# payloads.net
KiCad netlist of a schematic drawn in EAGLE
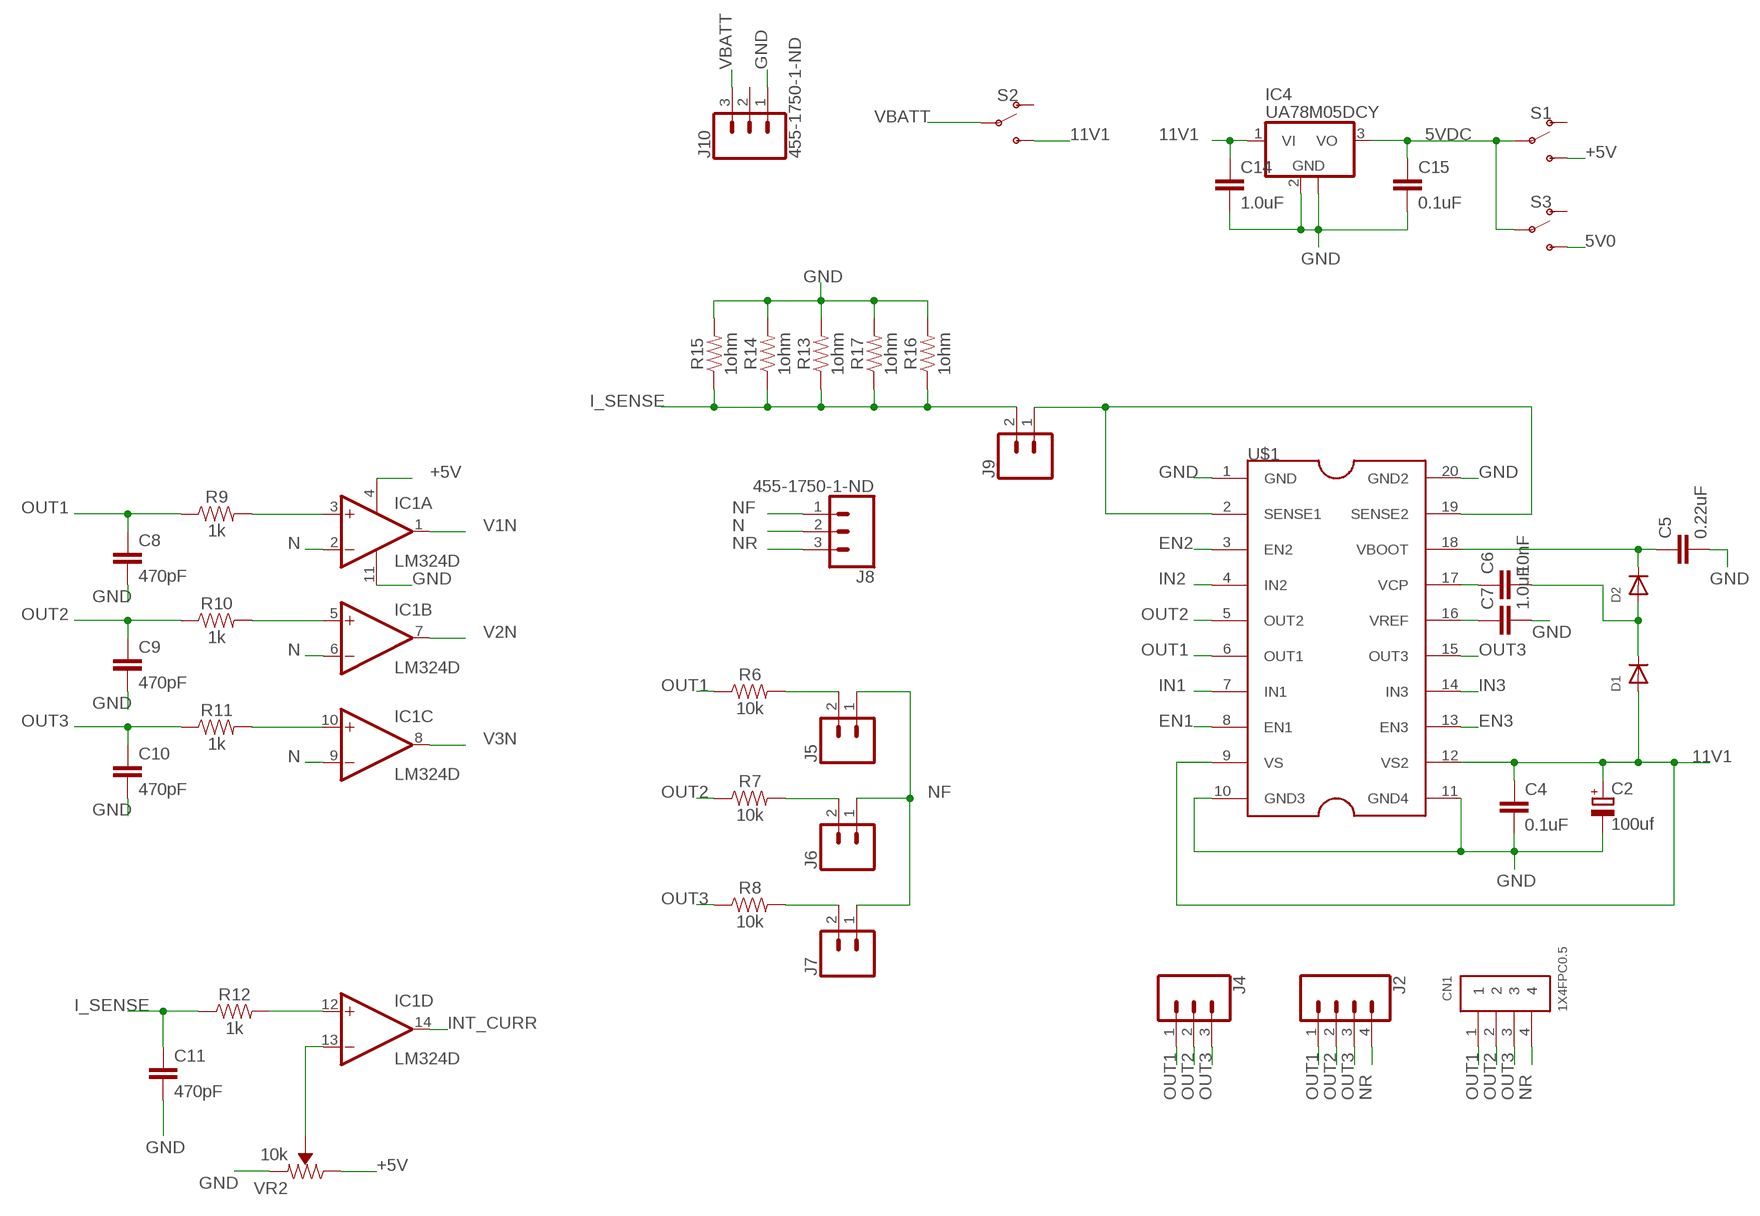
[diagram p0: schematic, sheet 1, part 1 of 2]
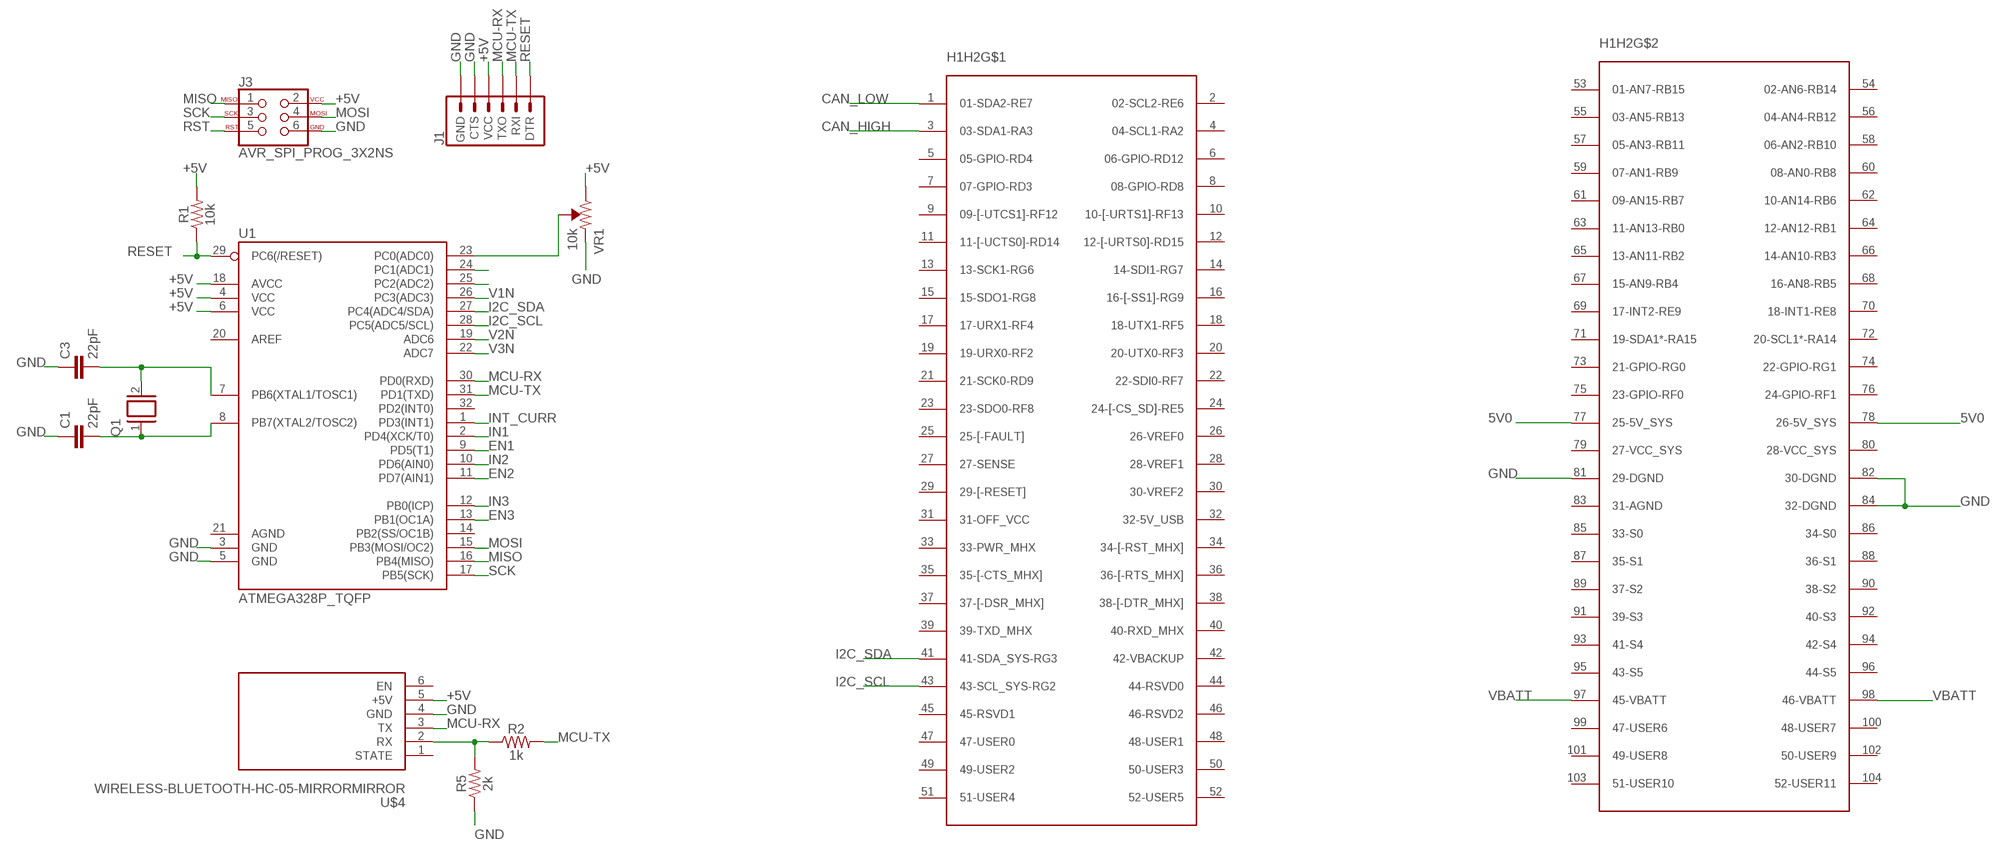
[diagram p1: schematic, sheet 1, part 2 of 2]

(export (version "E")
  (design (tool "Eeschema 10.0.6"))
  (components
    (comp (ref "C1")
      (value "22pF")
      (footprint "eagle-import:1206")
      (libsource (lib "eagle-import") (part "2.2UF-1206-50V-10%"))
    )
    (comp (ref "C2")
      (value "100uf")
      (footprint "eagle-import:C_6032-28R")
      (libsource (lib "eagle-import") (part "CPOL-EUC/6032-28R"))
    )
    (comp (ref "C3")
      (value "22pF")
      (footprint "eagle-import:1206")
      (libsource (lib "eagle-import") (part "2.2UF-1206-50V-10%"))
    )
    (comp (ref "C4")
      (value "0.1uF")
      (footprint "eagle-import:0603")
      (libsource (lib "eagle-import") (part "0.1UF-0603-100V-10%"))
    )
    (comp (ref "C5")
      (value "0.22uF")
      (footprint "eagle-import:0603")
      (libsource (lib "eagle-import") (part "0.22UF-0603-25V-10%"))
    )
    (comp (ref "C6")
      (value "10nF")
      (footprint "eagle-import:0603")
      (libsource (lib "eagle-import") (part "10NF-0603-50V-10%"))
    )
    (comp (ref "C7")
      (value "1.0uF")
      (footprint "eagle-import:0603")
      (libsource (lib "eagle-import") (part "1.0UF-0603-16V-10%"))
    )
    (comp (ref "C8")
      (value "470pF")
      (footprint "eagle-import:0603")
      (libsource (lib "eagle-import") (part "470PF-0603-50V-5%"))
    )
    (comp (ref "C9")
      (value "470pF")
      (footprint "eagle-import:0603")
      (libsource (lib "eagle-import") (part "470PF-0603-50V-5%"))
    )
    (comp (ref "C10")
      (value "470pF")
      (footprint "eagle-import:0603")
      (libsource (lib "eagle-import") (part "470PF-0603-50V-5%"))
    )
    (comp (ref "C11")
      (value "470pF")
      (footprint "eagle-import:0603")
      (libsource (lib "eagle-import") (part "470PF-0603-50V-5%"))
    )
    (comp (ref "C14")
      (value "1.0uF")
      (footprint "eagle-import:1206")
      (libsource (lib "eagle-import") (part "1.0UF-1206-50V-10%"))
    )
    (comp (ref "C15")
      (value "0.1uF")
      (footprint "eagle-import:1206")
      (libsource (lib "eagle-import") (part "1.0UF-1206-50V-10%"))
    )
    (comp (ref "CN1")
      (value "1X4FPC0.5")
      (footprint "eagle-import:FPC_0.5MM-4")
      (libsource (lib "eagle-import") (part "1X4FPC0.5"))
    )
    (comp (ref "D1")
      (value "DIODESOD-123")
      (footprint "eagle-import:SOD-123")
      (libsource (lib "eagle-import") (part "DIODESOD-123"))
    )
    (comp (ref "D2")
      (value "DIODESOD-123")
      (footprint "eagle-import:SOD-123")
      (libsource (lib "eagle-import") (part "DIODESOD-123"))
    )
    (comp (ref "H1H2")
      (value "PC104_CONN")
      (footprint "eagle-import:PC_104")
      (libsource (lib "eagle-import") (part "PC104_CONN"))
    )
    (comp (ref "IC1")
      (value "LM324D")
      (footprint "eagle-import:SO14")
      (libsource (lib "eagle-import") (part "LM324D"))
    )
    (comp (ref "IC4")
      (value "UA78M05DCY")
      (footprint "eagle-import:SOT223")
      (libsource (lib "eagle-import") (part "UA78MDCY05"))
    )
    (comp (ref "J1")
      (value "6_PIN_SERIAL_TARGET")
      (footprint "eagle-import:1X06")
      (libsource (lib "eagle-import") (part "6_PIN_SERIAL_TARGET"))
    )
    (comp (ref "J2")
      (value "CONN_04")
      (footprint "eagle-import:1X04")
      (libsource (lib "eagle-import") (part "CONN_04"))
    )
    (comp (ref "J3")
      (value "AVR_SPI_PROG_3X2NS")
      (footprint "eagle-import:2X3-NS")
      (libsource (lib "eagle-import") (part "AVR_SPI_PROG_3X2NS"))
    )
    (comp (ref "J4")
      (value "CONN_03-SCREW-5MM")
      (footprint "eagle-import:SCREWTERMINAL-5MM-3")
      (libsource (lib "eagle-import") (part "CONN_03-SCREW-5MM"))
    )
    (comp (ref "J5")
      (value "CONN_02")
      (footprint "eagle-import:1X02")
      (libsource (lib "eagle-import") (part "CONN_02"))
    )
    (comp (ref "J6")
      (value "CONN_02")
      (footprint "eagle-import:1X02")
      (libsource (lib "eagle-import") (part "CONN_02"))
    )
    (comp (ref "J7")
      (value "CONN_02")
      (footprint "eagle-import:1X02")
      (libsource (lib "eagle-import") (part "CONN_02"))
    )
    (comp (ref "J8")
      (value "455-1750-1-ND")
      (footprint "eagle-import:1X03")
      (libsource (lib "eagle-import") (part "CONN_03"))
    )
    (comp (ref "J9")
      (value "CONN_02")
      (footprint "eagle-import:1X02")
      (libsource (lib "eagle-import") (part "CONN_02"))
    )
    (comp (ref "J10")
      (value "455-1750-1-ND")
      (footprint "eagle-import:1X03")
      (libsource (lib "eagle-import") (part "CONN_03"))
    )
    (comp (ref "Q1")
      (value "XTAL/S")
      (footprint "eagle-import:QS")
      (libsource (lib "eagle-import") (part "XTAL/S"))
    )
    (comp (ref "R1")
      (value "10k")
      (footprint "eagle-import:1206")
      (libsource (lib "eagle-import") (part "RESISTOR1206"))
    )
    (comp (ref "R2")
      (value "1k")
      (footprint "eagle-import:AXIAL-0.3")
      (libsource (lib "eagle-import") (part "resistors-longpads_1KOHM-HORIZ-1/4W-5%"))
    )
    (comp (ref "R5")
      (value "2k")
      (footprint "eagle-import:AXIAL-0.3")
      (libsource (lib "eagle-import") (part "resistors-longpads_RESISTORAXIAL-0.3"))
    )
    (comp (ref "R6")
      (value "10k")
      (footprint "eagle-import:AXIAL-0.3")
      (libsource (lib "eagle-import") (part "10KOHM-HORIZ-1/4W-1%"))
    )
    (comp (ref "R7")
      (value "10k")
      (footprint "eagle-import:AXIAL-0.3")
      (libsource (lib "eagle-import") (part "10KOHM-HORIZ-1/4W-1%"))
    )
    (comp (ref "R8")
      (value "10k")
      (footprint "eagle-import:AXIAL-0.3")
      (libsource (lib "eagle-import") (part "10KOHM-HORIZ-1/4W-1%"))
    )
    (comp (ref "R9")
      (value "1k")
      (footprint "eagle-import:0603")
      (libsource (lib "eagle-import") (part "1KOHM-0603-1/10W-1%"))
    )
    (comp (ref "R10")
      (value "1k")
      (footprint "eagle-import:0603")
      (libsource (lib "eagle-import") (part "1KOHM-0603-1/10W-1%"))
    )
    (comp (ref "R11")
      (value "1k")
      (footprint "eagle-import:0603")
      (libsource (lib "eagle-import") (part "1KOHM-0603-1/10W-1%"))
    )
    (comp (ref "R12")
      (value "1k")
      (footprint "eagle-import:0603")
      (libsource (lib "eagle-import") (part "1KOHM-0603-1/10W-1%"))
    )
    (comp (ref "R13")
      (value "1ohm")
      (footprint "eagle-import:AXIAL-0.3")
      (libsource (lib "eagle-import") (part "1KOHM-HORIZ-1/4W-1%"))
    )
    (comp (ref "R14")
      (value "1ohm")
      (footprint "eagle-import:AXIAL-0.3")
      (libsource (lib "eagle-import") (part "1KOHM-HORIZ-1/4W-1%"))
    )
    (comp (ref "R15")
      (value "1ohm")
      (footprint "eagle-import:AXIAL-0.3")
      (libsource (lib "eagle-import") (part "1KOHM-HORIZ-1/4W-1%"))
    )
    (comp (ref "R16")
      (value "1ohm")
      (footprint "eagle-import:AXIAL-0.3")
      (libsource (lib "eagle-import") (part "1KOHM-HORIZ-1/4W-1%"))
    )
    (comp (ref "R17")
      (value "1ohm")
      (footprint "eagle-import:AXIAL-0.3")
      (libsource (lib "eagle-import") (part "1KOHM-HORIZ-1/4W-1%"))
    )
    (comp (ref "S1")
      (value "SWITCH-SPDT-PTH-11.6X4.0MM")
      (footprint "eagle-import:SWITCH_SPDT_PTH_11.6X4.0MM")
      (libsource (lib "eagle-import") (part "SWITCH-SPDT-PTH-11.6X4.0MM"))
    )
    (comp (ref "S2")
      (value "SWITCH-SPDT-PTH-11.6X4.0MM")
      (footprint "eagle-import:SWITCH_SPDT_PTH_11.6X4.0MM")
      (libsource (lib "eagle-import") (part "SWITCH-SPDT-PTH-11.6X4.0MM"))
    )
    (comp (ref "S3")
      (value "SWITCH-SPDT-PTH-11.6X4.0MM")
      (footprint "eagle-import:SWITCH_SPDT_PTH_11.6X4.0MM")
      (libsource (lib "eagle-import") (part "SWITCH-SPDT-PTH-11.6X4.0MM"))
    )
    (comp (ref "U$1")
      (value "L6234PD")
      (footprint "eagle-import:SO20")
      (libsource (lib "eagle-import") (part "L6234PD"))
    )
    (comp (ref "U$4")
      (value "WIRELESS-BLUETOOTH-HC-05-MIRRORMIRROR")
      (footprint "eagle-import:WIRELESS-BLUETOOTH-HC-05-MIRROR")
      (libsource (lib "eagle-import") (part "WIRELESS-BLUETOOTH-HC-05-MIRRORMIRROR"))
    )
    (comp (ref "U1")
      (value "ATMEGA328P_TQFP")
      (footprint "eagle-import:TQFP32-08")
      (libsource (lib "eagle-import") (part "ATMEGA328P_TQFP"))
    )
    (comp (ref "VR1")
      (value "10k")
      (footprint "eagle-import:TRIMPOT-PTH-3386U")
      (libsource (lib "eagle-import") (part "TRIMPOT-PTH-10MM-KNOB-1/2W-10%"))
    )
    (comp (ref "VR2")
      (value "10k")
      (footprint "eagle-import:TRIMPOT-PTH-3386U")
      (libsource (lib "eagle-import") (part "TRIMPOT-PTH-10MM-KNOB-1/2W-10%"))
    )
  )
  (nets
    (net (code "1") (name "/+5V") (class "Default")
      (node (ref "IC1") (pin "4") (pinfunction "V+_4") (pintype "power_in"))
      (node (ref "J1") (pin "4") (pinfunction "VCC_4") (pintype "passive"))
      (node (ref "J3") (pin "2") (pinfunction "2_2") (pintype "passive"))
      (node (ref "R1") (pin "2") (pinfunction "2_2") (pintype "passive"))
      (node (ref "S1") (pin "3") (pinfunction "S_3") (pintype "passive"))
      (node (ref "U$4") (pin "5") (pinfunction "+5V_5") (pintype "power_in"))
      (node (ref "U1") (pin "18") (pinfunction "AVCC_18") (pintype "bidirectional"))
      (node (ref "U1") (pin "4") (pinfunction "VCC_4") (pintype "bidirectional"))
      (node (ref "U1") (pin "6") (pinfunction "VCC_6") (pintype "bidirectional"))
      (node (ref "VR1") (pin "3") (pinfunction "CW_3") (pintype "passive"))
      (node (ref "VR2") (pin "3") (pinfunction "CW_3") (pintype "passive"))
    )
    (net (code "2") (name "/5V0") (class "Default")
      (node (ref "H1H2") (pin "77") (pinfunction "25-5V_SYS_77") (pintype "bidirectional"))
      (node (ref "H1H2") (pin "78") (pinfunction "26-5V_SYS_78") (pintype "bidirectional"))
      (node (ref "S3") (pin "3") (pinfunction "S_3") (pintype "passive"))
    )
    (net (code "3") (name "/5VDC") (class "Default")
      (node (ref "C15") (pin "1") (pinfunction "1_1") (pintype "passive"))
      (node (ref "IC4") (pin "3") (pinfunction "VO_3") (pintype "passive"))
      (node (ref "S1") (pin "2") (pinfunction "P_2") (pintype "passive"))
      (node (ref "S3") (pin "2") (pinfunction "P_2") (pintype "passive"))
    )
    (net (code "4") (name "/11V1") (class "Default")
      (node (ref "C14") (pin "1") (pinfunction "1_1") (pintype "passive"))
      (node (ref "C2") (pin "+") (pinfunction "+_+") (pintype "passive"))
      (node (ref "C4") (pin "1") (pinfunction "1_1") (pintype "passive"))
      (node (ref "D1") (pin "A") (pinfunction "A_A") (pintype "passive"))
      (node (ref "IC4") (pin "1") (pinfunction "VI_1") (pintype "input"))
      (node (ref "S2") (pin "3") (pinfunction "S_3") (pintype "passive"))
      (node (ref "U$1") (pin "12") (pinfunction "VS2_12") (pintype "power_in"))
      (node (ref "U$1") (pin "9") (pinfunction "VS_9") (pintype "power_in"))
    )
    (net (code "5") (name "/CAN_HIGH") (class "Default")
      (node (ref "H1H2") (pin "3") (pinfunction "03-SDA1-RA3_3") (pintype "bidirectional"))
    )
    (net (code "6") (name "/CAN_LOW") (class "Default")
      (node (ref "H1H2") (pin "1") (pinfunction "01-SDA2-RE7_1") (pintype "bidirectional"))
    )
    (net (code "7") (name "/EN1") (class "Default")
      (node (ref "U$1") (pin "8") (pinfunction "EN1_8") (pintype "bidirectional"))
      (node (ref "U1") (pin "9") (pinfunction "PD5(T1)_9") (pintype "bidirectional"))
    )
    (net (code "8") (name "/EN2") (class "Default")
      (node (ref "U$1") (pin "3") (pinfunction "EN2_3") (pintype "bidirectional"))
      (node (ref "U1") (pin "11") (pinfunction "PD7(AIN1)_11") (pintype "bidirectional"))
    )
    (net (code "9") (name "/EN3") (class "Default")
      (node (ref "U$1") (pin "13") (pinfunction "EN3_13") (pintype "bidirectional"))
      (node (ref "U1") (pin "13") (pinfunction "PB1(OC1A)_13") (pintype "bidirectional"))
    )
    (net (code "10") (name "/GND") (class "Default")
      (node (ref "C1") (pin "1") (pinfunction "1_1") (pintype "passive"))
      (node (ref "C10") (pin "2") (pinfunction "2_2") (pintype "passive"))
      (node (ref "C11") (pin "2") (pinfunction "2_2") (pintype "passive"))
      (node (ref "C14") (pin "2") (pinfunction "2_2") (pintype "passive"))
      (node (ref "C15") (pin "2") (pinfunction "2_2") (pintype "passive"))
      (node (ref "C2") (pin "-") (pinfunction "-_-") (pintype "passive"))
      (node (ref "C3") (pin "1") (pinfunction "1_1") (pintype "passive"))
      (node (ref "C4") (pin "2") (pinfunction "2_2") (pintype "passive"))
      (node (ref "C5") (pin "2") (pinfunction "2_2") (pintype "passive"))
      (node (ref "C7") (pin "2") (pinfunction "2_2") (pintype "passive"))
      (node (ref "C8") (pin "2") (pinfunction "2_2") (pintype "passive"))
      (node (ref "C9") (pin "2") (pinfunction "2_2") (pintype "passive"))
      (node (ref "H1H2") (pin "81") (pinfunction "29-DGND_81") (pintype "bidirectional"))
      (node (ref "H1H2") (pin "82") (pinfunction "30-DGND_82") (pintype "bidirectional"))
      (node (ref "H1H2") (pin "84") (pinfunction "32-DGND_84") (pintype "bidirectional"))
      (node (ref "IC1") (pin "11") (pinfunction "V-_11") (pintype "power_in"))
      (node (ref "IC4") (pin "2") (pinfunction "GND_2") (pintype "passive"))
      (node (ref "IC4") (pin "4") (pinfunction "GND_4") (pintype "passive"))
      (node (ref "J1") (pin "5") (pinfunction "CTS_5") (pintype "passive"))
      (node (ref "J1") (pin "6") (pinfunction "GND_6") (pintype "passive"))
      (node (ref "J10") (pin "1") (pinfunction "1_1") (pintype "passive"))
      (node (ref "J3") (pin "6") (pinfunction "6_6") (pintype "passive"))
      (node (ref "R13") (pin "P$2") (pinfunction "2_P$2") (pintype "passive"))
      (node (ref "R14") (pin "P$2") (pinfunction "2_P$2") (pintype "passive"))
      (node (ref "R15") (pin "P$2") (pinfunction "2_P$2") (pintype "passive"))
      (node (ref "R16") (pin "P$2") (pinfunction "2_P$2") (pintype "passive"))
      (node (ref "R17") (pin "P$2") (pinfunction "2_P$2") (pintype "passive"))
      (node (ref "R5") (pin "P$1") (pinfunction "1_P$1") (pintype "passive"))
      (node (ref "U$1") (pin "1") (pinfunction "GND_1") (pintype "bidirectional"))
      (node (ref "U$1") (pin "10") (pinfunction "GND3_10") (pintype "bidirectional"))
      (node (ref "U$1") (pin "11") (pinfunction "GND4_11") (pintype "bidirectional"))
      (node (ref "U$1") (pin "20") (pinfunction "GND2_20") (pintype "bidirectional"))
      (node (ref "U$4") (pin "4") (pinfunction "GND_4") (pintype "power_in"))
      (node (ref "U1") (pin "3") (pinfunction "GND_3") (pintype "bidirectional"))
      (node (ref "U1") (pin "5") (pinfunction "GND_5") (pintype "bidirectional"))
      (node (ref "VR1") (pin "1") (pinfunction "CCW_1") (pintype "passive"))
      (node (ref "VR2") (pin "1") (pinfunction "CCW_1") (pintype "passive"))
    )
    (net (code "11") (name "/I2C_SCL") (class "Default")
      (node (ref "H1H2") (pin "43") (pinfunction "43-SCL_SYS-RG2_43") (pintype "bidirectional"))
      (node (ref "U1") (pin "28") (pinfunction "PC5(ADC5/SCL)_28") (pintype "bidirectional"))
    )
    (net (code "12") (name "/I2C_SDA") (class "Default")
      (node (ref "H1H2") (pin "41") (pinfunction "41-SDA_SYS-RG3_41") (pintype "bidirectional"))
      (node (ref "U1") (pin "27") (pinfunction "PC4(ADC4/SDA)_27") (pintype "bidirectional"))
    )
    (net (code "13") (name "/IN1") (class "Default")
      (node (ref "U$1") (pin "7") (pinfunction "IN1_7") (pintype "bidirectional"))
      (node (ref "U1") (pin "2") (pinfunction "PD4(XCK/T0)_2") (pintype "bidirectional"))
    )
    (net (code "14") (name "/IN2") (class "Default")
      (node (ref "U$1") (pin "4") (pinfunction "IN2_4") (pintype "bidirectional"))
      (node (ref "U1") (pin "10") (pinfunction "PD6(AIN0)_10") (pintype "bidirectional"))
    )
    (net (code "15") (name "/IN3") (class "Default")
      (node (ref "U$1") (pin "14") (pinfunction "IN3_14") (pintype "bidirectional"))
      (node (ref "U1") (pin "12") (pinfunction "PB0(ICP)_12") (pintype "bidirectional"))
    )
    (net (code "16") (name "/INT_CURR") (class "Default")
      (node (ref "IC1") (pin "14") (pinfunction "OUT_14") (pintype "output"))
      (node (ref "U1") (pin "1") (pinfunction "PD3(INT1)_1") (pintype "bidirectional"))
    )
    (net (code "17") (name "/I_SENSE") (class "Default")
      (node (ref "C11") (pin "1") (pinfunction "1_1") (pintype "passive"))
      (node (ref "J9") (pin "2") (pinfunction "2_2") (pintype "passive"))
      (node (ref "R12") (pin "1") (pinfunction "1_1") (pintype "passive"))
      (node (ref "R13") (pin "P$1") (pinfunction "1_P$1") (pintype "passive"))
      (node (ref "R14") (pin "P$1") (pinfunction "1_P$1") (pintype "passive"))
      (node (ref "R15") (pin "P$1") (pinfunction "1_P$1") (pintype "passive"))
      (node (ref "R16") (pin "P$1") (pinfunction "1_P$1") (pintype "passive"))
      (node (ref "R17") (pin "P$1") (pinfunction "1_P$1") (pintype "passive"))
    )
    (net (code "18") (name "/MCU-RX") (class "Default")
      (node (ref "J1") (pin "3") (pinfunction "TXO_3") (pintype "passive"))
      (node (ref "U$4") (pin "3") (pinfunction "TX_3") (pintype "bidirectional"))
      (node (ref "U1") (pin "30") (pinfunction "PD0(RXD)_30") (pintype "bidirectional"))
    )
    (net (code "19") (name "/MCU-TX") (class "Default")
      (node (ref "J1") (pin "2") (pinfunction "RXI_2") (pintype "passive"))
      (node (ref "R2") (pin "P$2") (pinfunction "2_P$2") (pintype "passive"))
      (node (ref "U1") (pin "31") (pinfunction "PD1(TXD)_31") (pintype "bidirectional"))
    )
    (net (code "20") (name "/MISO") (class "Default")
      (node (ref "J3") (pin "1") (pinfunction "1_1") (pintype "passive"))
      (node (ref "U1") (pin "16") (pinfunction "PB4(MISO)_16") (pintype "bidirectional"))
    )
    (net (code "21") (name "/MOSI") (class "Default")
      (node (ref "J3") (pin "4") (pinfunction "4_4") (pintype "passive"))
      (node (ref "U1") (pin "15") (pinfunction "PB3(MOSI/OC2)_15") (pintype "bidirectional"))
    )
    (net (code "22") (name "/N") (class "Default")
      (node (ref "IC1") (pin "2") (pinfunction "-IN_2") (pintype "input"))
      (node (ref "IC1") (pin "6") (pinfunction "-IN_6") (pintype "input"))
      (node (ref "IC1") (pin "9") (pinfunction "-IN_9") (pintype "input"))
      (node (ref "J8") (pin "2") (pinfunction "2_2") (pintype "passive"))
    )
    (net (code "23") (name "/NF") (class "Default")
      (node (ref "J5") (pin "1") (pinfunction "1_1") (pintype "passive"))
      (node (ref "J6") (pin "1") (pinfunction "1_1") (pintype "passive"))
      (node (ref "J7") (pin "1") (pinfunction "1_1") (pintype "passive"))
      (node (ref "J8") (pin "1") (pinfunction "1_1") (pintype "passive"))
    )
    (net (code "24") (name "/NR") (class "Default")
      (node (ref "CN1") (pin "4") (pinfunction "4_4") (pintype "bidirectional"))
      (node (ref "J2") (pin "4") (pinfunction "4_4") (pintype "passive"))
      (node (ref "J8") (pin "3") (pinfunction "3_3") (pintype "passive"))
    )
    (net (code "25") (name "/OUT1") (class "Default")
      (node (ref "C8") (pin "1") (pinfunction "1_1") (pintype "passive"))
      (node (ref "CN1") (pin "1") (pinfunction "1_1") (pintype "bidirectional"))
      (node (ref "J2") (pin "1") (pinfunction "1_1") (pintype "passive"))
      (node (ref "J4") (pin "1") (pinfunction "1_1") (pintype "passive"))
      (node (ref "R6") (pin "P$1") (pinfunction "1_P$1") (pintype "passive"))
      (node (ref "R9") (pin "1") (pinfunction "1_1") (pintype "passive"))
      (node (ref "U$1") (pin "6") (pinfunction "OUT1_6") (pintype "bidirectional"))
    )
    (net (code "26") (name "/OUT2") (class "Default")
      (node (ref "C9") (pin "1") (pinfunction "1_1") (pintype "passive"))
      (node (ref "CN1") (pin "2") (pinfunction "2_2") (pintype "bidirectional"))
      (node (ref "J2") (pin "2") (pinfunction "2_2") (pintype "passive"))
      (node (ref "J4") (pin "2") (pinfunction "2_2") (pintype "passive"))
      (node (ref "R10") (pin "1") (pinfunction "1_1") (pintype "passive"))
      (node (ref "R7") (pin "P$1") (pinfunction "1_P$1") (pintype "passive"))
      (node (ref "U$1") (pin "5") (pinfunction "OUT2_5") (pintype "bidirectional"))
    )
    (net (code "27") (name "/OUT3") (class "Default")
      (node (ref "C10") (pin "1") (pinfunction "1_1") (pintype "passive"))
      (node (ref "CN1") (pin "3") (pinfunction "3_3") (pintype "bidirectional"))
      (node (ref "J2") (pin "3") (pinfunction "3_3") (pintype "passive"))
      (node (ref "J4") (pin "3") (pinfunction "3_3") (pintype "passive"))
      (node (ref "R11") (pin "1") (pinfunction "1_1") (pintype "passive"))
      (node (ref "R8") (pin "P$1") (pinfunction "1_P$1") (pintype "passive"))
      (node (ref "U$1") (pin "15") (pinfunction "OUT3_15") (pintype "bidirectional"))
    )
    (net (code "28") (name "/RESET") (class "Default")
      (node (ref "J1") (pin "1") (pinfunction "DTR_1") (pintype "passive"))
      (node (ref "R1") (pin "1") (pinfunction "1_1") (pintype "passive"))
      (node (ref "U1") (pin "29") (pinfunction "PC6(/RESET)_29") (pintype "bidirectional"))
    )
    (net (code "29") (name "/RST") (class "Default")
      (node (ref "J3") (pin "5") (pinfunction "5_5") (pintype "passive"))
    )
    (net (code "30") (name "/SCK") (class "Default")
      (node (ref "J3") (pin "3") (pinfunction "3_3") (pintype "passive"))
      (node (ref "U1") (pin "17") (pinfunction "PB5(SCK)_17") (pintype "bidirectional"))
    )
    (net (code "31") (name "/V1N") (class "Default")
      (node (ref "IC1") (pin "1") (pinfunction "OUT_1") (pintype "output"))
      (node (ref "U1") (pin "26") (pinfunction "PC3(ADC3)_26") (pintype "bidirectional"))
    )
    (net (code "32") (name "/V2N") (class "Default")
      (node (ref "IC1") (pin "7") (pinfunction "OUT_7") (pintype "output"))
      (node (ref "U1") (pin "19") (pinfunction "ADC6_19") (pintype "bidirectional"))
    )
    (net (code "33") (name "/V3N") (class "Default")
      (node (ref "IC1") (pin "8") (pinfunction "OUT_8") (pintype "output"))
      (node (ref "U1") (pin "22") (pinfunction "ADC7_22") (pintype "bidirectional"))
    )
    (net (code "34") (name "/VBATT") (class "Default")
      (node (ref "H1H2") (pin "97") (pinfunction "45-VBATT_97") (pintype "bidirectional"))
      (node (ref "H1H2") (pin "98") (pinfunction "46-VBATT_98") (pintype "bidirectional"))
      (node (ref "J10") (pin "3") (pinfunction "3_3") (pintype "passive"))
      (node (ref "S2") (pin "2") (pinfunction "P_2") (pintype "passive"))
    )
    (net (code "35") (name "Net-(C6-Pad2)") (class "Default")
      (node (ref "C6") (pin "2") (pinfunction "2_2") (pintype "passive"))
      (node (ref "D1") (pin "C") (pinfunction "C_C") (pintype "passive"))
      (node (ref "D2") (pin "A") (pinfunction "A_A") (pintype "passive"))
    )
    (net (code "36") (name "Net-(IC1A-+IN)") (class "Default")
      (node (ref "IC1") (pin "3") (pinfunction "+IN_3") (pintype "input"))
      (node (ref "R9") (pin "2") (pinfunction "2_2") (pintype "passive"))
    )
    (net (code "37") (name "Net-(IC1B-+IN)") (class "Default")
      (node (ref "IC1") (pin "5") (pinfunction "+IN_5") (pintype "input"))
      (node (ref "R10") (pin "2") (pinfunction "2_2") (pintype "passive"))
    )
    (net (code "38") (name "Net-(IC1C-+IN)") (class "Default")
      (node (ref "IC1") (pin "10") (pinfunction "+IN_10") (pintype "input"))
      (node (ref "R11") (pin "2") (pinfunction "2_2") (pintype "passive"))
    )
    (net (code "39") (name "Net-(IC1D-+IN)") (class "Default")
      (node (ref "IC1") (pin "12") (pinfunction "+IN_12") (pintype "input"))
      (node (ref "R12") (pin "2") (pinfunction "2_2") (pintype "passive"))
    )
    (net (code "40") (name "Net-(IC1D--IN)") (class "Default")
      (node (ref "IC1") (pin "13") (pinfunction "-IN_13") (pintype "input"))
      (node (ref "VR2") (pin "2") (pinfunction "WIPER_2") (pintype "passive"))
    )
    (net (code "41") (name "Net-(R2-1)") (class "Default")
      (node (ref "R2") (pin "P$1") (pinfunction "1_P$1") (pintype "passive"))
      (node (ref "R5") (pin "P$2") (pinfunction "2_P$2") (pintype "passive"))
      (node (ref "U$4") (pin "2") (pinfunction "RX_2") (pintype "bidirectional"))
    )
    (net (code "42") (name "Net-(R6-2)") (class "Default")
      (node (ref "J5") (pin "2") (pinfunction "2_2") (pintype "passive"))
      (node (ref "R6") (pin "P$2") (pinfunction "2_P$2") (pintype "passive"))
    )
    (net (code "43") (name "Net-(R7-2)") (class "Default")
      (node (ref "J6") (pin "2") (pinfunction "2_2") (pintype "passive"))
      (node (ref "R7") (pin "P$2") (pinfunction "2_P$2") (pintype "passive"))
    )
    (net (code "44") (name "Net-(R8-2)") (class "Default")
      (node (ref "J7") (pin "2") (pinfunction "2_2") (pintype "passive"))
      (node (ref "R8") (pin "P$2") (pinfunction "2_P$2") (pintype "passive"))
    )
    (net (code "45") (name "Net-(U$1-SENSE1)") (class "Default")
      (node (ref "J9") (pin "1") (pinfunction "1_1") (pintype "passive"))
      (node (ref "U$1") (pin "19") (pinfunction "SENSE2_19") (pintype "bidirectional"))
      (node (ref "U$1") (pin "2") (pinfunction "SENSE1_2") (pintype "bidirectional"))
    )
    (net (code "46") (name "Net-(U$1-VBOOT)") (class "Default")
      (node (ref "C5") (pin "1") (pinfunction "1_1") (pintype "passive"))
      (node (ref "D2") (pin "C") (pinfunction "C_C") (pintype "passive"))
      (node (ref "U$1") (pin "18") (pinfunction "VBOOT_18") (pintype "bidirectional"))
    )
    (net (code "47") (name "Net-(U$1-VCP)") (class "Default")
      (node (ref "C6") (pin "1") (pinfunction "1_1") (pintype "passive"))
      (node (ref "U$1") (pin "17") (pinfunction "VCP_17") (pintype "bidirectional"))
    )
    (net (code "48") (name "Net-(U$1-VREF)") (class "Default")
      (node (ref "C7") (pin "1") (pinfunction "1_1") (pintype "passive"))
      (node (ref "U$1") (pin "16") (pinfunction "VREF_16") (pintype "bidirectional"))
    )
    (net (code "49") (name "Net-(U1-PB6(XTAL1{slash}TOSC1))") (class "Default")
      (node (ref "C3") (pin "2") (pinfunction "2_2") (pintype "passive"))
      (node (ref "Q1") (pin "2") (pinfunction "2_2") (pintype "passive"))
      (node (ref "U1") (pin "7") (pinfunction "PB6(XTAL1/TOSC1)_7") (pintype "bidirectional"))
    )
    (net (code "50") (name "Net-(U1-PB7(XTAL2{slash}TOSC2))") (class "Default")
      (node (ref "C1") (pin "2") (pinfunction "2_2") (pintype "passive"))
      (node (ref "Q1") (pin "1") (pinfunction "1_1") (pintype "passive"))
      (node (ref "U1") (pin "8") (pinfunction "PB7(XTAL2/TOSC2)_8") (pintype "bidirectional"))
    )
    (net (code "51") (name "Net-(U1-PC0(ADC0))") (class "Default")
      (node (ref "U1") (pin "23") (pinfunction "PC0(ADC0)_23") (pintype "bidirectional"))
      (node (ref "VR1") (pin "2") (pinfunction "WIPER_2") (pintype "passive"))
    )
    (net (code "52") (name "unconnected-(H1H2A-02-SCL2-RE6-Pad2)") (class "Default")
      (node (ref "H1H2") (pin "2") (pinfunction "02-SCL2-RE6_2") (pintype "bidirectional"))
    )
    (net (code "53") (name "unconnected-(H1H2A-04-SCL1-RA2-Pad4)") (class "Default")
      (node (ref "H1H2") (pin "4") (pinfunction "04-SCL1-RA2_4") (pintype "bidirectional"))
    )
    (net (code "54") (name "unconnected-(H1H2A-05-GPIO-RD4-Pad5)") (class "Default")
      (node (ref "H1H2") (pin "5") (pinfunction "05-GPIO-RD4_5") (pintype "bidirectional"))
    )
    (net (code "55") (name "unconnected-(H1H2A-06-GPIO-RD12-Pad6)") (class "Default")
      (node (ref "H1H2") (pin "6") (pinfunction "06-GPIO-RD12_6") (pintype "bidirectional"))
    )
    (net (code "56") (name "unconnected-(H1H2A-07-GPIO-RD3-Pad7)") (class "Default")
      (node (ref "H1H2") (pin "7") (pinfunction "07-GPIO-RD3_7") (pintype "bidirectional"))
    )
    (net (code "57") (name "unconnected-(H1H2A-08-GPIO-RD8-Pad8)") (class "Default")
      (node (ref "H1H2") (pin "8") (pinfunction "08-GPIO-RD8_8") (pintype "bidirectional"))
    )
    (net (code "58") (name "unconnected-(H1H2A-09-[-UTCS1]-RF12-Pad9)") (class "Default")
      (node (ref "H1H2") (pin "9") (pinfunction "09-[-UTCS1]-RF12_9") (pintype "bidirectional"))
    )
    (net (code "59") (name "unconnected-(H1H2A-10-[-URTS1]-RF13-Pad10)") (class "Default")
      (node (ref "H1H2") (pin "10") (pinfunction "10-[-URTS1]-RF13_10") (pintype "bidirectional"))
    )
    (net (code "60") (name "unconnected-(H1H2A-11-[-UCTS0]-RD14-Pad11)") (class "Default")
      (node (ref "H1H2") (pin "11") (pinfunction "11-[-UCTS0]-RD14_11") (pintype "bidirectional"))
    )
    (net (code "61") (name "unconnected-(H1H2A-12-[-URTS0]-RD15-Pad12)") (class "Default")
      (node (ref "H1H2") (pin "12") (pinfunction "12-[-URTS0]-RD15_12") (pintype "bidirectional"))
    )
    (net (code "62") (name "unconnected-(H1H2A-13-SCK1-RG6-Pad13)") (class "Default")
      (node (ref "H1H2") (pin "13") (pinfunction "13-SCK1-RG6_13") (pintype "bidirectional"))
    )
    (net (code "63") (name "unconnected-(H1H2A-14-SDI1-RG7-Pad14)") (class "Default")
      (node (ref "H1H2") (pin "14") (pinfunction "14-SDI1-RG7_14") (pintype "bidirectional"))
    )
    (net (code "64") (name "unconnected-(H1H2A-15-SDO1-RG8-Pad15)") (class "Default")
      (node (ref "H1H2") (pin "15") (pinfunction "15-SDO1-RG8_15") (pintype "bidirectional"))
    )
    (net (code "65") (name "unconnected-(H1H2A-16-[-SS1]-RG9-Pad16)") (class "Default")
      (node (ref "H1H2") (pin "16") (pinfunction "16-[-SS1]-RG9_16") (pintype "bidirectional"))
    )
    (net (code "66") (name "unconnected-(H1H2A-17-URX1-RF4-Pad17)") (class "Default")
      (node (ref "H1H2") (pin "17") (pinfunction "17-URX1-RF4_17") (pintype "bidirectional"))
    )
    (net (code "67") (name "unconnected-(H1H2A-18-UTX1-RF5-Pad18)") (class "Default")
      (node (ref "H1H2") (pin "18") (pinfunction "18-UTX1-RF5_18") (pintype "bidirectional"))
    )
    (net (code "68") (name "unconnected-(H1H2A-19-URX0-RF2-Pad19)") (class "Default")
      (node (ref "H1H2") (pin "19") (pinfunction "19-URX0-RF2_19") (pintype "bidirectional"))
    )
    (net (code "69") (name "unconnected-(H1H2A-20-UTX0-RF3-Pad20)") (class "Default")
      (node (ref "H1H2") (pin "20") (pinfunction "20-UTX0-RF3_20") (pintype "bidirectional"))
    )
    (net (code "70") (name "unconnected-(H1H2A-21-SCK0-RD9-Pad21)") (class "Default")
      (node (ref "H1H2") (pin "21") (pinfunction "21-SCK0-RD9_21") (pintype "bidirectional"))
    )
    (net (code "71") (name "unconnected-(H1H2A-22-SDI0-RF7-Pad22)") (class "Default")
      (node (ref "H1H2") (pin "22") (pinfunction "22-SDI0-RF7_22") (pintype "bidirectional"))
    )
    (net (code "72") (name "unconnected-(H1H2A-23-SDO0-RF8-Pad23)") (class "Default")
      (node (ref "H1H2") (pin "23") (pinfunction "23-SDO0-RF8_23") (pintype "bidirectional"))
    )
    (net (code "73") (name "unconnected-(H1H2A-24-[-CS_SD]-RE5-Pad24)") (class "Default")
      (node (ref "H1H2") (pin "24") (pinfunction "24-[-CS_SD]-RE5_24") (pintype "bidirectional"))
    )
    (net (code "74") (name "unconnected-(H1H2A-25-[-FAULT]-Pad25)") (class "Default")
      (node (ref "H1H2") (pin "25") (pinfunction "25-[-FAULT]_25") (pintype "bidirectional"))
    )
    (net (code "75") (name "unconnected-(H1H2A-26-VREF0-Pad26)") (class "Default")
      (node (ref "H1H2") (pin "26") (pinfunction "26-VREF0_26") (pintype "bidirectional"))
    )
    (net (code "76") (name "unconnected-(H1H2A-27-SENSE-Pad27)") (class "Default")
      (node (ref "H1H2") (pin "27") (pinfunction "27-SENSE_27") (pintype "bidirectional"))
    )
    (net (code "77") (name "unconnected-(H1H2A-28-VREF1-Pad28)") (class "Default")
      (node (ref "H1H2") (pin "28") (pinfunction "28-VREF1_28") (pintype "bidirectional"))
    )
    (net (code "78") (name "unconnected-(H1H2A-29-[-RESET]-Pad29)") (class "Default")
      (node (ref "H1H2") (pin "29") (pinfunction "29-[-RESET]_29") (pintype "bidirectional"))
    )
    (net (code "79") (name "unconnected-(H1H2A-30-VREF2-Pad30)") (class "Default")
      (node (ref "H1H2") (pin "30") (pinfunction "30-VREF2_30") (pintype "bidirectional"))
    )
    (net (code "80") (name "unconnected-(H1H2A-31-OFF_VCC-Pad31)") (class "Default")
      (node (ref "H1H2") (pin "31") (pinfunction "31-OFF_VCC_31") (pintype "bidirectional"))
    )
    (net (code "81") (name "unconnected-(H1H2A-32-5V_USB-Pad32)") (class "Default")
      (node (ref "H1H2") (pin "32") (pinfunction "32-5V_USB_32") (pintype "bidirectional"))
    )
    (net (code "82") (name "unconnected-(H1H2A-33-PWR_MHX-Pad33)") (class "Default")
      (node (ref "H1H2") (pin "33") (pinfunction "33-PWR_MHX_33") (pintype "bidirectional"))
    )
    (net (code "83") (name "unconnected-(H1H2A-34-[-RST_MHX]-Pad34)") (class "Default")
      (node (ref "H1H2") (pin "34") (pinfunction "34-[-RST_MHX]_34") (pintype "bidirectional"))
    )
    (net (code "84") (name "unconnected-(H1H2A-35-[-CTS_MHX]-Pad35)") (class "Default")
      (node (ref "H1H2") (pin "35") (pinfunction "35-[-CTS_MHX]_35") (pintype "bidirectional"))
    )
    (net (code "85") (name "unconnected-(H1H2A-36-[-RTS_MHX]-Pad36)") (class "Default")
      (node (ref "H1H2") (pin "36") (pinfunction "36-[-RTS_MHX]_36") (pintype "bidirectional"))
    )
    (net (code "86") (name "unconnected-(H1H2A-37-[-DSR_MHX]-Pad37)") (class "Default")
      (node (ref "H1H2") (pin "37") (pinfunction "37-[-DSR_MHX]_37") (pintype "bidirectional"))
    )
    (net (code "87") (name "unconnected-(H1H2A-38-[-DTR_MHX]-Pad38)") (class "Default")
      (node (ref "H1H2") (pin "38") (pinfunction "38-[-DTR_MHX]_38") (pintype "bidirectional"))
    )
    (net (code "88") (name "unconnected-(H1H2A-39-TXD_MHX-Pad39)") (class "Default")
      (node (ref "H1H2") (pin "39") (pinfunction "39-TXD_MHX_39") (pintype "bidirectional"))
    )
    (net (code "89") (name "unconnected-(H1H2A-40-RXD_MHX-Pad40)") (class "Default")
      (node (ref "H1H2") (pin "40") (pinfunction "40-RXD_MHX_40") (pintype "bidirectional"))
    )
    (net (code "90") (name "unconnected-(H1H2A-42-VBACKUP-Pad42)") (class "Default")
      (node (ref "H1H2") (pin "42") (pinfunction "42-VBACKUP_42") (pintype "bidirectional"))
    )
    (net (code "91") (name "unconnected-(H1H2A-44-RSVD0-Pad44)") (class "Default")
      (node (ref "H1H2") (pin "44") (pinfunction "44-RSVD0_44") (pintype "bidirectional"))
    )
    (net (code "92") (name "unconnected-(H1H2A-45-RSVD1-Pad45)") (class "Default")
      (node (ref "H1H2") (pin "45") (pinfunction "45-RSVD1_45") (pintype "bidirectional"))
    )
    (net (code "93") (name "unconnected-(H1H2A-46-RSVD2-Pad46)") (class "Default")
      (node (ref "H1H2") (pin "46") (pinfunction "46-RSVD2_46") (pintype "bidirectional"))
    )
    (net (code "94") (name "unconnected-(H1H2A-47-USER0-Pad47)") (class "Default")
      (node (ref "H1H2") (pin "47") (pinfunction "47-USER0_47") (pintype "bidirectional"))
    )
    (net (code "95") (name "unconnected-(H1H2A-48-USER1-Pad48)") (class "Default")
      (node (ref "H1H2") (pin "48") (pinfunction "48-USER1_48") (pintype "bidirectional"))
    )
    (net (code "96") (name "unconnected-(H1H2A-49-USER2-Pad49)") (class "Default")
      (node (ref "H1H2") (pin "49") (pinfunction "49-USER2_49") (pintype "bidirectional"))
    )
    (net (code "97") (name "unconnected-(H1H2A-50-USER3-Pad50)") (class "Default")
      (node (ref "H1H2") (pin "50") (pinfunction "50-USER3_50") (pintype "bidirectional"))
    )
    (net (code "98") (name "unconnected-(H1H2A-51-USER4-Pad51)") (class "Default")
      (node (ref "H1H2") (pin "51") (pinfunction "51-USER4_51") (pintype "bidirectional"))
    )
    (net (code "99") (name "unconnected-(H1H2A-52-USER5-Pad52)") (class "Default")
      (node (ref "H1H2") (pin "52") (pinfunction "52-USER5_52") (pintype "bidirectional"))
    )
    (net (code "100") (name "unconnected-(H1H2B-01-AN7-RB15-Pad53)") (class "Default")
      (node (ref "H1H2") (pin "53") (pinfunction "01-AN7-RB15_53") (pintype "bidirectional"))
    )
    (net (code "101") (name "unconnected-(H1H2B-02-AN6-RB14-Pad54)") (class "Default")
      (node (ref "H1H2") (pin "54") (pinfunction "02-AN6-RB14_54") (pintype "bidirectional"))
    )
    (net (code "102") (name "unconnected-(H1H2B-03-AN5-RB13-Pad55)") (class "Default")
      (node (ref "H1H2") (pin "55") (pinfunction "03-AN5-RB13_55") (pintype "bidirectional"))
    )
    (net (code "103") (name "unconnected-(H1H2B-04-AN4-RB12-Pad56)") (class "Default")
      (node (ref "H1H2") (pin "56") (pinfunction "04-AN4-RB12_56") (pintype "bidirectional"))
    )
    (net (code "104") (name "unconnected-(H1H2B-05-AN3-RB11-Pad57)") (class "Default")
      (node (ref "H1H2") (pin "57") (pinfunction "05-AN3-RB11_57") (pintype "bidirectional"))
    )
    (net (code "105") (name "unconnected-(H1H2B-06-AN2-RB10-Pad58)") (class "Default")
      (node (ref "H1H2") (pin "58") (pinfunction "06-AN2-RB10_58") (pintype "bidirectional"))
    )
    (net (code "106") (name "unconnected-(H1H2B-07-AN1-RB9-Pad59)") (class "Default")
      (node (ref "H1H2") (pin "59") (pinfunction "07-AN1-RB9_59") (pintype "bidirectional"))
    )
    (net (code "107") (name "unconnected-(H1H2B-08-AN0-RB8-Pad60)") (class "Default")
      (node (ref "H1H2") (pin "60") (pinfunction "08-AN0-RB8_60") (pintype "bidirectional"))
    )
    (net (code "108") (name "unconnected-(H1H2B-09-AN15-RB7-Pad61)") (class "Default")
      (node (ref "H1H2") (pin "61") (pinfunction "09-AN15-RB7_61") (pintype "bidirectional"))
    )
    (net (code "109") (name "unconnected-(H1H2B-10-AN14-RB6-Pad62)") (class "Default")
      (node (ref "H1H2") (pin "62") (pinfunction "10-AN14-RB6_62") (pintype "bidirectional"))
    )
    (net (code "110") (name "unconnected-(H1H2B-11-AN13-RB0-Pad63)") (class "Default")
      (node (ref "H1H2") (pin "63") (pinfunction "11-AN13-RB0_63") (pintype "bidirectional"))
    )
    (net (code "111") (name "unconnected-(H1H2B-12-AN12-RB1-Pad64)") (class "Default")
      (node (ref "H1H2") (pin "64") (pinfunction "12-AN12-RB1_64") (pintype "bidirectional"))
    )
    (net (code "112") (name "unconnected-(H1H2B-13-AN11-RB2-Pad65)") (class "Default")
      (node (ref "H1H2") (pin "65") (pinfunction "13-AN11-RB2_65") (pintype "bidirectional"))
    )
    (net (code "113") (name "unconnected-(H1H2B-14-AN10-RB3-Pad66)") (class "Default")
      (node (ref "H1H2") (pin "66") (pinfunction "14-AN10-RB3_66") (pintype "bidirectional"))
    )
    (net (code "114") (name "unconnected-(H1H2B-15-AN9-RB4-Pad67)") (class "Default")
      (node (ref "H1H2") (pin "67") (pinfunction "15-AN9-RB4_67") (pintype "bidirectional"))
    )
    (net (code "115") (name "unconnected-(H1H2B-16-AN8-RB5-Pad68)") (class "Default")
      (node (ref "H1H2") (pin "68") (pinfunction "16-AN8-RB5_68") (pintype "bidirectional"))
    )
    (net (code "116") (name "unconnected-(H1H2B-17-INT2-RE9-Pad69)") (class "Default")
      (node (ref "H1H2") (pin "69") (pinfunction "17-INT2-RE9_69") (pintype "bidirectional"))
    )
    (net (code "117") (name "unconnected-(H1H2B-18-INT1-RE8-Pad70)") (class "Default")
      (node (ref "H1H2") (pin "70") (pinfunction "18-INT1-RE8_70") (pintype "bidirectional"))
    )
    (net (code "118") (name "unconnected-(H1H2B-19-SDA1*-RA15-Pad71)") (class "Default")
      (node (ref "H1H2") (pin "71") (pinfunction "19-SDA1*-RA15_71") (pintype "bidirectional"))
    )
    (net (code "119") (name "unconnected-(H1H2B-20-SCL1*-RA14-Pad72)") (class "Default")
      (node (ref "H1H2") (pin "72") (pinfunction "20-SCL1*-RA14_72") (pintype "bidirectional"))
    )
    (net (code "120") (name "unconnected-(H1H2B-21-GPIO-RG0-Pad73)") (class "Default")
      (node (ref "H1H2") (pin "73") (pinfunction "21-GPIO-RG0_73") (pintype "bidirectional"))
    )
    (net (code "121") (name "unconnected-(H1H2B-22-GPIO-RG1-Pad74)") (class "Default")
      (node (ref "H1H2") (pin "74") (pinfunction "22-GPIO-RG1_74") (pintype "bidirectional"))
    )
    (net (code "122") (name "unconnected-(H1H2B-23-GPIO-RF0-Pad75)") (class "Default")
      (node (ref "H1H2") (pin "75") (pinfunction "23-GPIO-RF0_75") (pintype "bidirectional"))
    )
    (net (code "123") (name "unconnected-(H1H2B-24-GPIO-RF1-Pad76)") (class "Default")
      (node (ref "H1H2") (pin "76") (pinfunction "24-GPIO-RF1_76") (pintype "bidirectional"))
    )
    (net (code "124") (name "unconnected-(H1H2B-27-VCC_SYS-Pad79)") (class "Default")
      (node (ref "H1H2") (pin "79") (pinfunction "27-VCC_SYS_79") (pintype "bidirectional"))
    )
    (net (code "125") (name "unconnected-(H1H2B-28-VCC_SYS-Pad80)") (class "Default")
      (node (ref "H1H2") (pin "80") (pinfunction "28-VCC_SYS_80") (pintype "bidirectional"))
    )
    (net (code "126") (name "unconnected-(H1H2B-31-AGND-Pad83)") (class "Default")
      (node (ref "H1H2") (pin "83") (pinfunction "31-AGND_83") (pintype "bidirectional"))
    )
    (net (code "127") (name "unconnected-(H1H2B-33-S0-Pad85)") (class "Default")
      (node (ref "H1H2") (pin "85") (pinfunction "33-S0_85") (pintype "bidirectional"))
    )
    (net (code "128") (name "unconnected-(H1H2B-34-S0-Pad86)") (class "Default")
      (node (ref "H1H2") (pin "86") (pinfunction "34-S0_86") (pintype "bidirectional"))
    )
    (net (code "129") (name "unconnected-(H1H2B-35-S1-Pad87)") (class "Default")
      (node (ref "H1H2") (pin "87") (pinfunction "35-S1_87") (pintype "bidirectional"))
    )
    (net (code "130") (name "unconnected-(H1H2B-36-S1-Pad88)") (class "Default")
      (node (ref "H1H2") (pin "88") (pinfunction "36-S1_88") (pintype "bidirectional"))
    )
    (net (code "131") (name "unconnected-(H1H2B-37-S2-Pad89)") (class "Default")
      (node (ref "H1H2") (pin "89") (pinfunction "37-S2_89") (pintype "bidirectional"))
    )
    (net (code "132") (name "unconnected-(H1H2B-38-S2-Pad90)") (class "Default")
      (node (ref "H1H2") (pin "90") (pinfunction "38-S2_90") (pintype "bidirectional"))
    )
    (net (code "133") (name "unconnected-(H1H2B-39-S3-Pad91)") (class "Default")
      (node (ref "H1H2") (pin "91") (pinfunction "39-S3_91") (pintype "bidirectional"))
    )
    (net (code "134") (name "unconnected-(H1H2B-40-S3-Pad92)") (class "Default")
      (node (ref "H1H2") (pin "92") (pinfunction "40-S3_92") (pintype "bidirectional"))
    )
    (net (code "135") (name "unconnected-(H1H2B-41-S4-Pad93)") (class "Default")
      (node (ref "H1H2") (pin "93") (pinfunction "41-S4_93") (pintype "bidirectional"))
    )
    (net (code "136") (name "unconnected-(H1H2B-42-S4-Pad94)") (class "Default")
      (node (ref "H1H2") (pin "94") (pinfunction "42-S4_94") (pintype "bidirectional"))
    )
    (net (code "137") (name "unconnected-(H1H2B-43-S5-Pad95)") (class "Default")
      (node (ref "H1H2") (pin "95") (pinfunction "43-S5_95") (pintype "bidirectional"))
    )
    (net (code "138") (name "unconnected-(H1H2B-44-S5-Pad96)") (class "Default")
      (node (ref "H1H2") (pin "96") (pinfunction "44-S5_96") (pintype "bidirectional"))
    )
    (net (code "139") (name "unconnected-(H1H2B-47-USER6-Pad99)") (class "Default")
      (node (ref "H1H2") (pin "99") (pinfunction "47-USER6_99") (pintype "bidirectional"))
    )
    (net (code "140") (name "unconnected-(H1H2B-48-USER7-Pad100)") (class "Default")
      (node (ref "H1H2") (pin "100") (pinfunction "48-USER7_100") (pintype "bidirectional"))
    )
    (net (code "141") (name "unconnected-(H1H2B-49-USER8-Pad101)") (class "Default")
      (node (ref "H1H2") (pin "101") (pinfunction "49-USER8_101") (pintype "bidirectional"))
    )
    (net (code "142") (name "unconnected-(H1H2B-50-USER9-Pad102)") (class "Default")
      (node (ref "H1H2") (pin "102") (pinfunction "50-USER9_102") (pintype "bidirectional"))
    )
    (net (code "143") (name "unconnected-(H1H2B-51-USER10-Pad103)") (class "Default")
      (node (ref "H1H2") (pin "103") (pinfunction "51-USER10_103") (pintype "bidirectional"))
    )
    (net (code "144") (name "unconnected-(H1H2B-52-USER11-Pad104)") (class "Default")
      (node (ref "H1H2") (pin "104") (pinfunction "52-USER11_104") (pintype "bidirectional"))
    )
    (net (code "145") (name "unconnected-(J10-Pad2)") (class "Default")
      (node (ref "J10") (pin "2") (pinfunction "2_2") (pintype "passive"))
    )
    (net (code "146") (name "unconnected-(S1-O-Pad1)") (class "Default")
      (node (ref "S1") (pin "1") (pinfunction "O_1") (pintype "passive"))
    )
    (net (code "147") (name "unconnected-(S2-O-Pad1)") (class "Default")
      (node (ref "S2") (pin "1") (pinfunction "O_1") (pintype "passive"))
    )
    (net (code "148") (name "unconnected-(S3-O-Pad1)") (class "Default")
      (node (ref "S3") (pin "1") (pinfunction "O_1") (pintype "passive"))
    )
    (net (code "149") (name "unconnected-(U$4-EN-Pad6)") (class "Default")
      (node (ref "U$4") (pin "6") (pinfunction "EN_6") (pintype "bidirectional"))
    )
    (net (code "150") (name "unconnected-(U$4-STATE-Pad1)") (class "Default")
      (node (ref "U$4") (pin "1") (pinfunction "STATE_1") (pintype "bidirectional"))
    )
    (net (code "151") (name "unconnected-(U1-AGND-Pad21)") (class "Default")
      (node (ref "U1") (pin "21") (pinfunction "AGND_21") (pintype "bidirectional"))
    )
    (net (code "152") (name "unconnected-(U1-AREF-Pad20)") (class "Default")
      (node (ref "U1") (pin "20") (pinfunction "AREF_20") (pintype "bidirectional"))
    )
    (net (code "153") (name "unconnected-(U1-PB2(SS{slash}OC1B)-Pad14)") (class "Default")
      (node (ref "U1") (pin "14") (pinfunction "PB2(SS/OC1B)_14") (pintype "bidirectional"))
    )
    (net (code "154") (name "unconnected-(U1-PC1(ADC1)-Pad24)") (class "Default")
      (node (ref "U1") (pin "24") (pinfunction "PC1(ADC1)_24") (pintype "bidirectional"))
    )
    (net (code "155") (name "unconnected-(U1-PC2(ADC2)-Pad25)") (class "Default")
      (node (ref "U1") (pin "25") (pinfunction "PC2(ADC2)_25") (pintype "bidirectional"))
    )
    (net (code "156") (name "unconnected-(U1-PD2(INT0)-Pad32)") (class "Default")
      (node (ref "U1") (pin "32") (pinfunction "PD2(INT0)_32") (pintype "bidirectional"))
    )
  )
)
